# CAN.net
KiCad netlist of a schematic drawn in Altium Designer
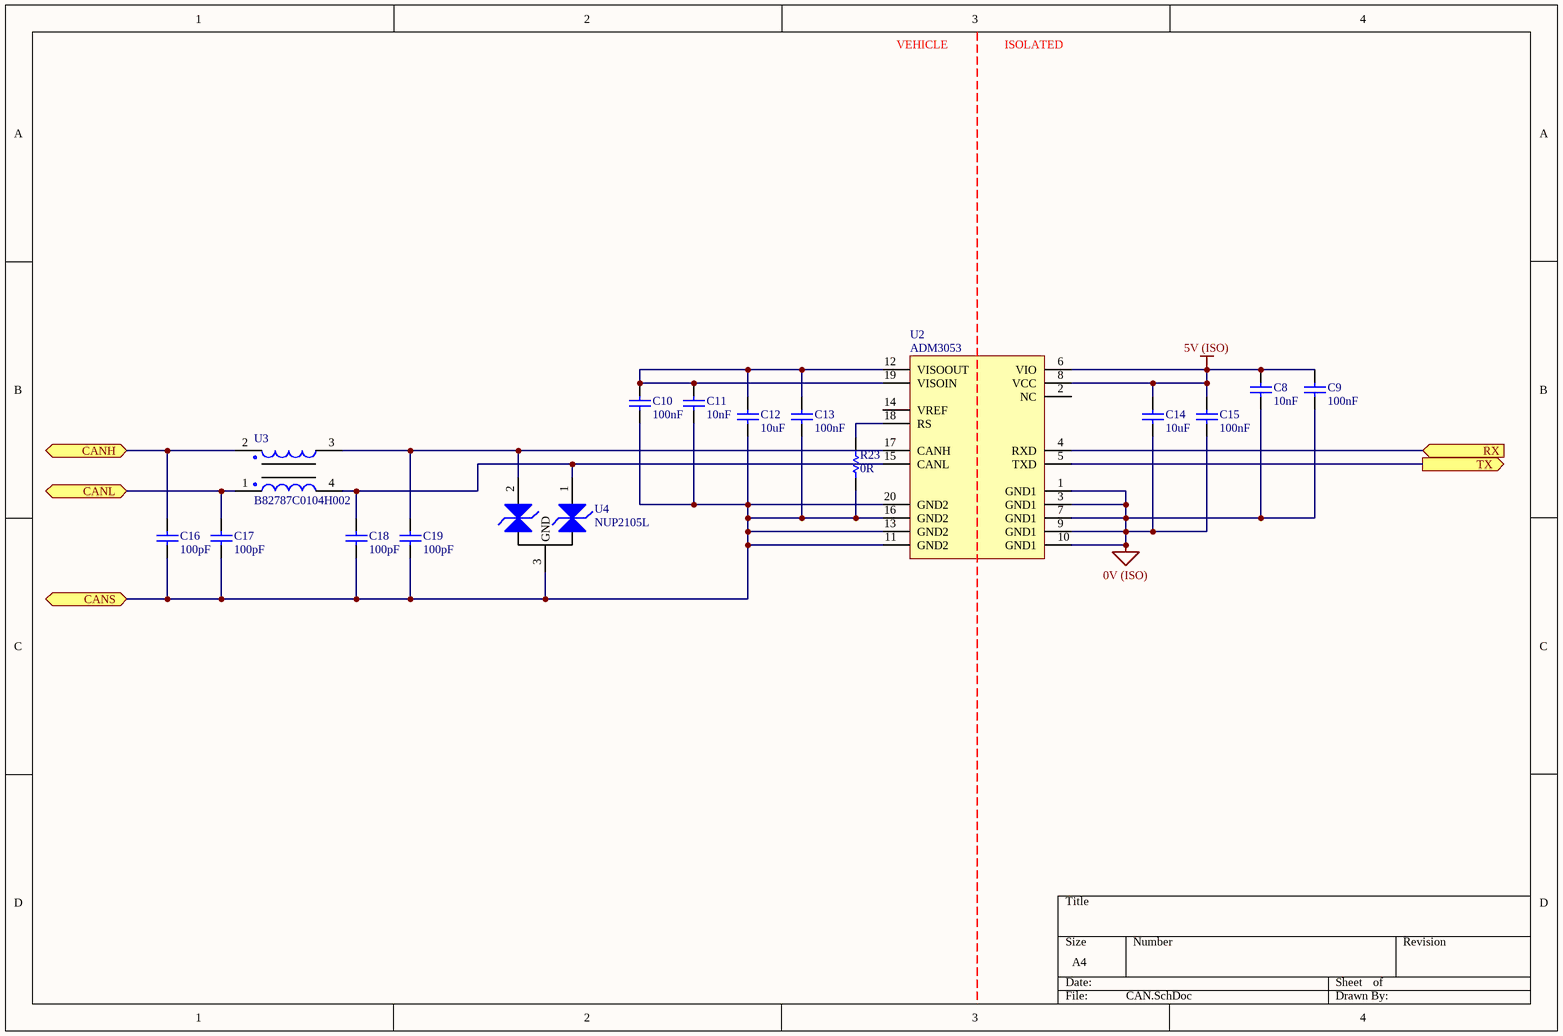
[diagram p0: CAN.SchDoc]

(export (version "E")
  (design (tool "Eeschema 10.0.6"))
  (components
    (comp (ref "C8")
      (value "10nF")
      (footprint "1206")
      (fields
        (field (name "PART NUMBER") "GCM3195C2A103JA16D")
        (field (name "TOLERANCE") "5%")
        (field (name "MANUFACTURER") "muRata")
      )
      (libsource (lib "ts_19-standard-library") (part "Capacitor"))
    )
    (comp (ref "C9")
      (value "100nF")
      (footprint "0805")
      (fields
        (field (name "PART NUMBER") "GCM21BR71E104KA37L")
        (field (name "TOLERANCE") "10%")
        (field (name "MANUFACTURER") "muRata")
      )
      (libsource (lib "ts_19-standard-library") (part "Capacitor"))
    )
    (comp (ref "C10")
      (value "100nF")
      (footprint "0805")
      (fields
        (field (name "PART NUMBER") "GCM21BR71E104KA37L")
        (field (name "TOLERANCE") "10%")
        (field (name "MANUFACTURER") "muRata")
      )
      (libsource (lib "ts_19-standard-library") (part "Capacitor"))
    )
    (comp (ref "C11")
      (value "10nF")
      (footprint "1206")
      (fields
        (field (name "PART NUMBER") "GCM3195C2A103JA16D")
        (field (name "TOLERANCE") "5%")
        (field (name "MANUFACTURER") "muRata")
      )
      (libsource (lib "ts_19-standard-library") (part "Capacitor"))
    )
    (comp (ref "C12")
      (value "10uF")
      (footprint "0805")
      (fields
        (field (name "PART NUMBER") "GRM21BR6YA106KE43L")
        (field (name "TOLERANCE") "10%")
        (field (name "MANUFACTURER") "muRata")
      )
      (libsource (lib "ts_19-standard-library") (part "Capacitor"))
    )
    (comp (ref "C13")
      (value "100nF")
      (footprint "0805")
      (fields
        (field (name "PART NUMBER") "GCM21BR71E104KA37L")
        (field (name "TOLERANCE") "10%")
        (field (name "MANUFACTURER") "muRata")
      )
      (libsource (lib "ts_19-standard-library") (part "Capacitor"))
    )
    (comp (ref "C14")
      (value "10uF")
      (footprint "0805")
      (fields
        (field (name "PART NUMBER") "GRM21BR6YA106KE43L")
        (field (name "TOLERANCE") "10%")
        (field (name "MANUFACTURER") "muRata")
      )
      (libsource (lib "ts_19-standard-library") (part "Capacitor"))
    )
    (comp (ref "C15")
      (value "100nF")
      (footprint "0805")
      (fields
        (field (name "PART NUMBER") "GCM21BR71E104KA37L")
        (field (name "TOLERANCE") "10%")
        (field (name "MANUFACTURER") "muRata")
      )
      (libsource (lib "ts_19-standard-library") (part "Capacitor"))
    )
    (comp (ref "C16")
      (value "100pF")
      (footprint "0805")
      (fields
        (field (name "PART NUMBER") "GCM21B5C1H101JA37L")
        (field (name "TOLERANCE") "5%")
        (field (name "MANUFACTURER") "muRata")
      )
      (libsource (lib "ts_19-standard-library") (part "Capacitor"))
    )
    (comp (ref "C17")
      (value "100pF")
      (footprint "0805")
      (fields
        (field (name "PART NUMBER") "GCM21B5C1H101JA37L")
        (field (name "TOLERANCE") "5%")
        (field (name "MANUFACTURER") "muRata")
      )
      (libsource (lib "ts_19-standard-library") (part "Capacitor"))
    )
    (comp (ref "C18")
      (value "100pF")
      (footprint "0805")
      (fields
        (field (name "PART NUMBER") "GCM21B5C1H101JA37L")
        (field (name "TOLERANCE") "5%")
        (field (name "MANUFACTURER") "muRata")
      )
      (libsource (lib "ts_19-standard-library") (part "Capacitor"))
    )
    (comp (ref "C19")
      (value "100pF")
      (footprint "0805")
      (fields
        (field (name "PART NUMBER") "GCM21B5C1H101JA37L")
        (field (name "TOLERANCE") "5%")
        (field (name "MANUFACTURER") "muRata")
      )
      (libsource (lib "ts_19-standard-library") (part "Capacitor"))
    )
    (comp (ref "R23")
      (value "0R")
      (footprint "0805")
      (fields
        (field (name "TOLERANCE") "0.01")
        (field (name "PART NUMBER") "RC0805FR070RL")
        (field (name "MANUFACTURER") "YAGEO")
      )
      (libsource (lib "ts_19-standard-library") (part "Resistor"))
    )
    (comp (ref "U2")
      (value "ADM3053")
      (footprint "AD SOIC-W 20")
      (description "Isolated CAN Transceiver")
      (fields
        (field (name "MANUFACTURER") "Analogue Devices")
        (field (name "DIGIKEY PART NUMBER") "ADM3053BRWZ-ND")
      )
      (libsource (lib "ts_19-standard-library") (part "ADM3053"))
    )
    (comp (ref "U3")
      (value "B82787C0104H002")
      (footprint "TDK 4-PC Pad")
      (description "Common mode choke intended for CANBUS 150mA 50V)")
      (fields
        (field (name "MANUFACTURER") "EPCOS (TDK)")
        (field (name "DIGIKEY PART NUMBER") "495-4598-2-ND")
      )
      (libsource (lib "ts_19-standard-library") (part "B82787C0104H002"))
    )
    (comp (ref "U4")
      (value "NUP2105L")
      (footprint "ON SOT-23")
      (description "Dual Line CAN Bus Protector")
      (fields
        (field (name "MANUFACTURER") "ON Semiconductor")
        (field (name "DIGIKEY PART NUMBER") "NUP2105LT1GOSCT-ND")
      )
      (libsource (lib "ts_19-standard-library") (part "NUP2105L"))
    )
  )
  (nets
    (net (code "1") (name "/CANH") (class "Default")
      (node (ref "C16") (pin "2") (pinfunction "2_2") (pintype "passive"))
      (node (ref "U3") (pin "2") (pinfunction "2_2") (pintype "passive"))
    )
    (net (code "2") (name "/CANL") (class "Default")
      (node (ref "C17") (pin "2") (pinfunction "2_2") (pintype "passive"))
      (node (ref "U3") (pin "1") (pinfunction "1_1") (pintype "passive"))
    )
    (net (code "3") (name "/CANS") (class "Default")
      (node (ref "C10") (pin "1") (pinfunction "1_1") (pintype "passive"))
      (node (ref "C11") (pin "1") (pinfunction "1_1") (pintype "passive"))
      (node (ref "C12") (pin "1") (pinfunction "1_1") (pintype "passive"))
      (node (ref "C13") (pin "1") (pinfunction "1_1") (pintype "passive"))
      (node (ref "C16") (pin "1") (pinfunction "1_1") (pintype "passive"))
      (node (ref "C17") (pin "1") (pinfunction "1_1") (pintype "passive"))
      (node (ref "C18") (pin "1") (pinfunction "1_1") (pintype "passive"))
      (node (ref "C19") (pin "1") (pinfunction "1_1") (pintype "passive"))
      (node (ref "R23") (pin "1") (pinfunction "1_1") (pintype "passive"))
      (node (ref "U2") (pin "11") (pinfunction "GND2_11") (pintype "passive"))
      (node (ref "U2") (pin "13") (pinfunction "GND2_13") (pintype "passive"))
      (node (ref "U2") (pin "16") (pinfunction "GND2_16") (pintype "passive"))
      (node (ref "U2") (pin "20") (pinfunction "GND2_20") (pintype "passive"))
      (node (ref "U4") (pin "3") (pinfunction "GND_3") (pintype "power_in"))
    )
    (net (code "4") (name "/RX") (class "Default")
      (node (ref "U2") (pin "4") (pinfunction "RXD_4") (pintype "passive"))
    )
    (net (code "5") (name "/TX") (class "Default")
      (node (ref "U2") (pin "5") (pinfunction "TXD_5") (pintype "passive"))
    )
    (net (code "6") (name "0V (ISO)") (class "Default")
      (node (ref "C14") (pin "1") (pinfunction "1_1") (pintype "passive"))
      (node (ref "C15") (pin "1") (pinfunction "1_1") (pintype "passive"))
      (node (ref "C8") (pin "1") (pinfunction "1_1") (pintype "passive"))
      (node (ref "C9") (pin "1") (pinfunction "1_1") (pintype "passive"))
      (node (ref "U2") (pin "1") (pinfunction "GND1_1") (pintype "passive"))
      (node (ref "U2") (pin "10") (pinfunction "GND1_10") (pintype "passive"))
      (node (ref "U2") (pin "3") (pinfunction "GND1_3") (pintype "passive"))
      (node (ref "U2") (pin "7") (pinfunction "GND1_7") (pintype "passive"))
      (node (ref "U2") (pin "9") (pinfunction "GND1_9") (pintype "passive"))
    )
    (net (code "7") (name "5V (ISO)") (class "Default")
      (node (ref "C14") (pin "2") (pinfunction "2_2") (pintype "passive"))
      (node (ref "C15") (pin "2") (pinfunction "2_2") (pintype "passive"))
      (node (ref "C8") (pin "2") (pinfunction "2_2") (pintype "passive"))
      (node (ref "C9") (pin "2") (pinfunction "2_2") (pintype "passive"))
      (node (ref "U2") (pin "6") (pinfunction "VIO_6") (pintype "passive"))
      (node (ref "U2") (pin "8") (pinfunction "VCC_8") (pintype "passive"))
    )
    (net (code "8") (name "Net-(U2-CANH)") (class "Default")
      (node (ref "C19") (pin "2") (pinfunction "2_2") (pintype "passive"))
      (node (ref "U2") (pin "17") (pinfunction "CANH_17") (pintype "passive"))
      (node (ref "U3") (pin "3") (pinfunction "3_3") (pintype "power_in"))
      (node (ref "U4") (pin "2") (pinfunction "CAN_L_2") (pintype "passive"))
    )
    (net (code "9") (name "Net-(U2-CANL)") (class "Default")
      (node (ref "C18") (pin "2") (pinfunction "2_2") (pintype "passive"))
      (node (ref "U2") (pin "15") (pinfunction "CANL_15") (pintype "passive"))
      (node (ref "U3") (pin "4") (pinfunction "4_4") (pintype "passive"))
      (node (ref "U4") (pin "1") (pinfunction "CAN_H_1") (pintype "passive"))
    )
    (net (code "10") (name "Net-(U2-RS)") (class "Default")
      (node (ref "R23") (pin "2") (pinfunction "2_2") (pintype "passive"))
      (node (ref "U2") (pin "18") (pinfunction "RS_18") (pintype "passive"))
    )
    (net (code "11") (name "Net-(U2-VISOIN)") (class "Default")
      (node (ref "C10") (pin "2") (pinfunction "2_2") (pintype "passive"))
      (node (ref "C11") (pin "2") (pinfunction "2_2") (pintype "passive"))
      (node (ref "C12") (pin "2") (pinfunction "2_2") (pintype "passive"))
      (node (ref "C13") (pin "2") (pinfunction "2_2") (pintype "passive"))
      (node (ref "U2") (pin "12") (pinfunction "VISOOUT_12") (pintype "passive"))
      (node (ref "U2") (pin "19") (pinfunction "VISOIN_19") (pintype "passive"))
    )
    (net (code "12") (name "unconnected-(U2-NC-Pad2)") (class "Default")
      (node (ref "U2") (pin "2") (pinfunction "NC_2") (pintype "passive"))
    )
    (net (code "13") (name "unconnected-(U2-VREF-Pad14)") (class "Default")
      (node (ref "U2") (pin "14") (pinfunction "VREF_14") (pintype "passive"))
    )
  )
)
